# MCU.net
KiCad netlist of a schematic drawn in Altium Designer
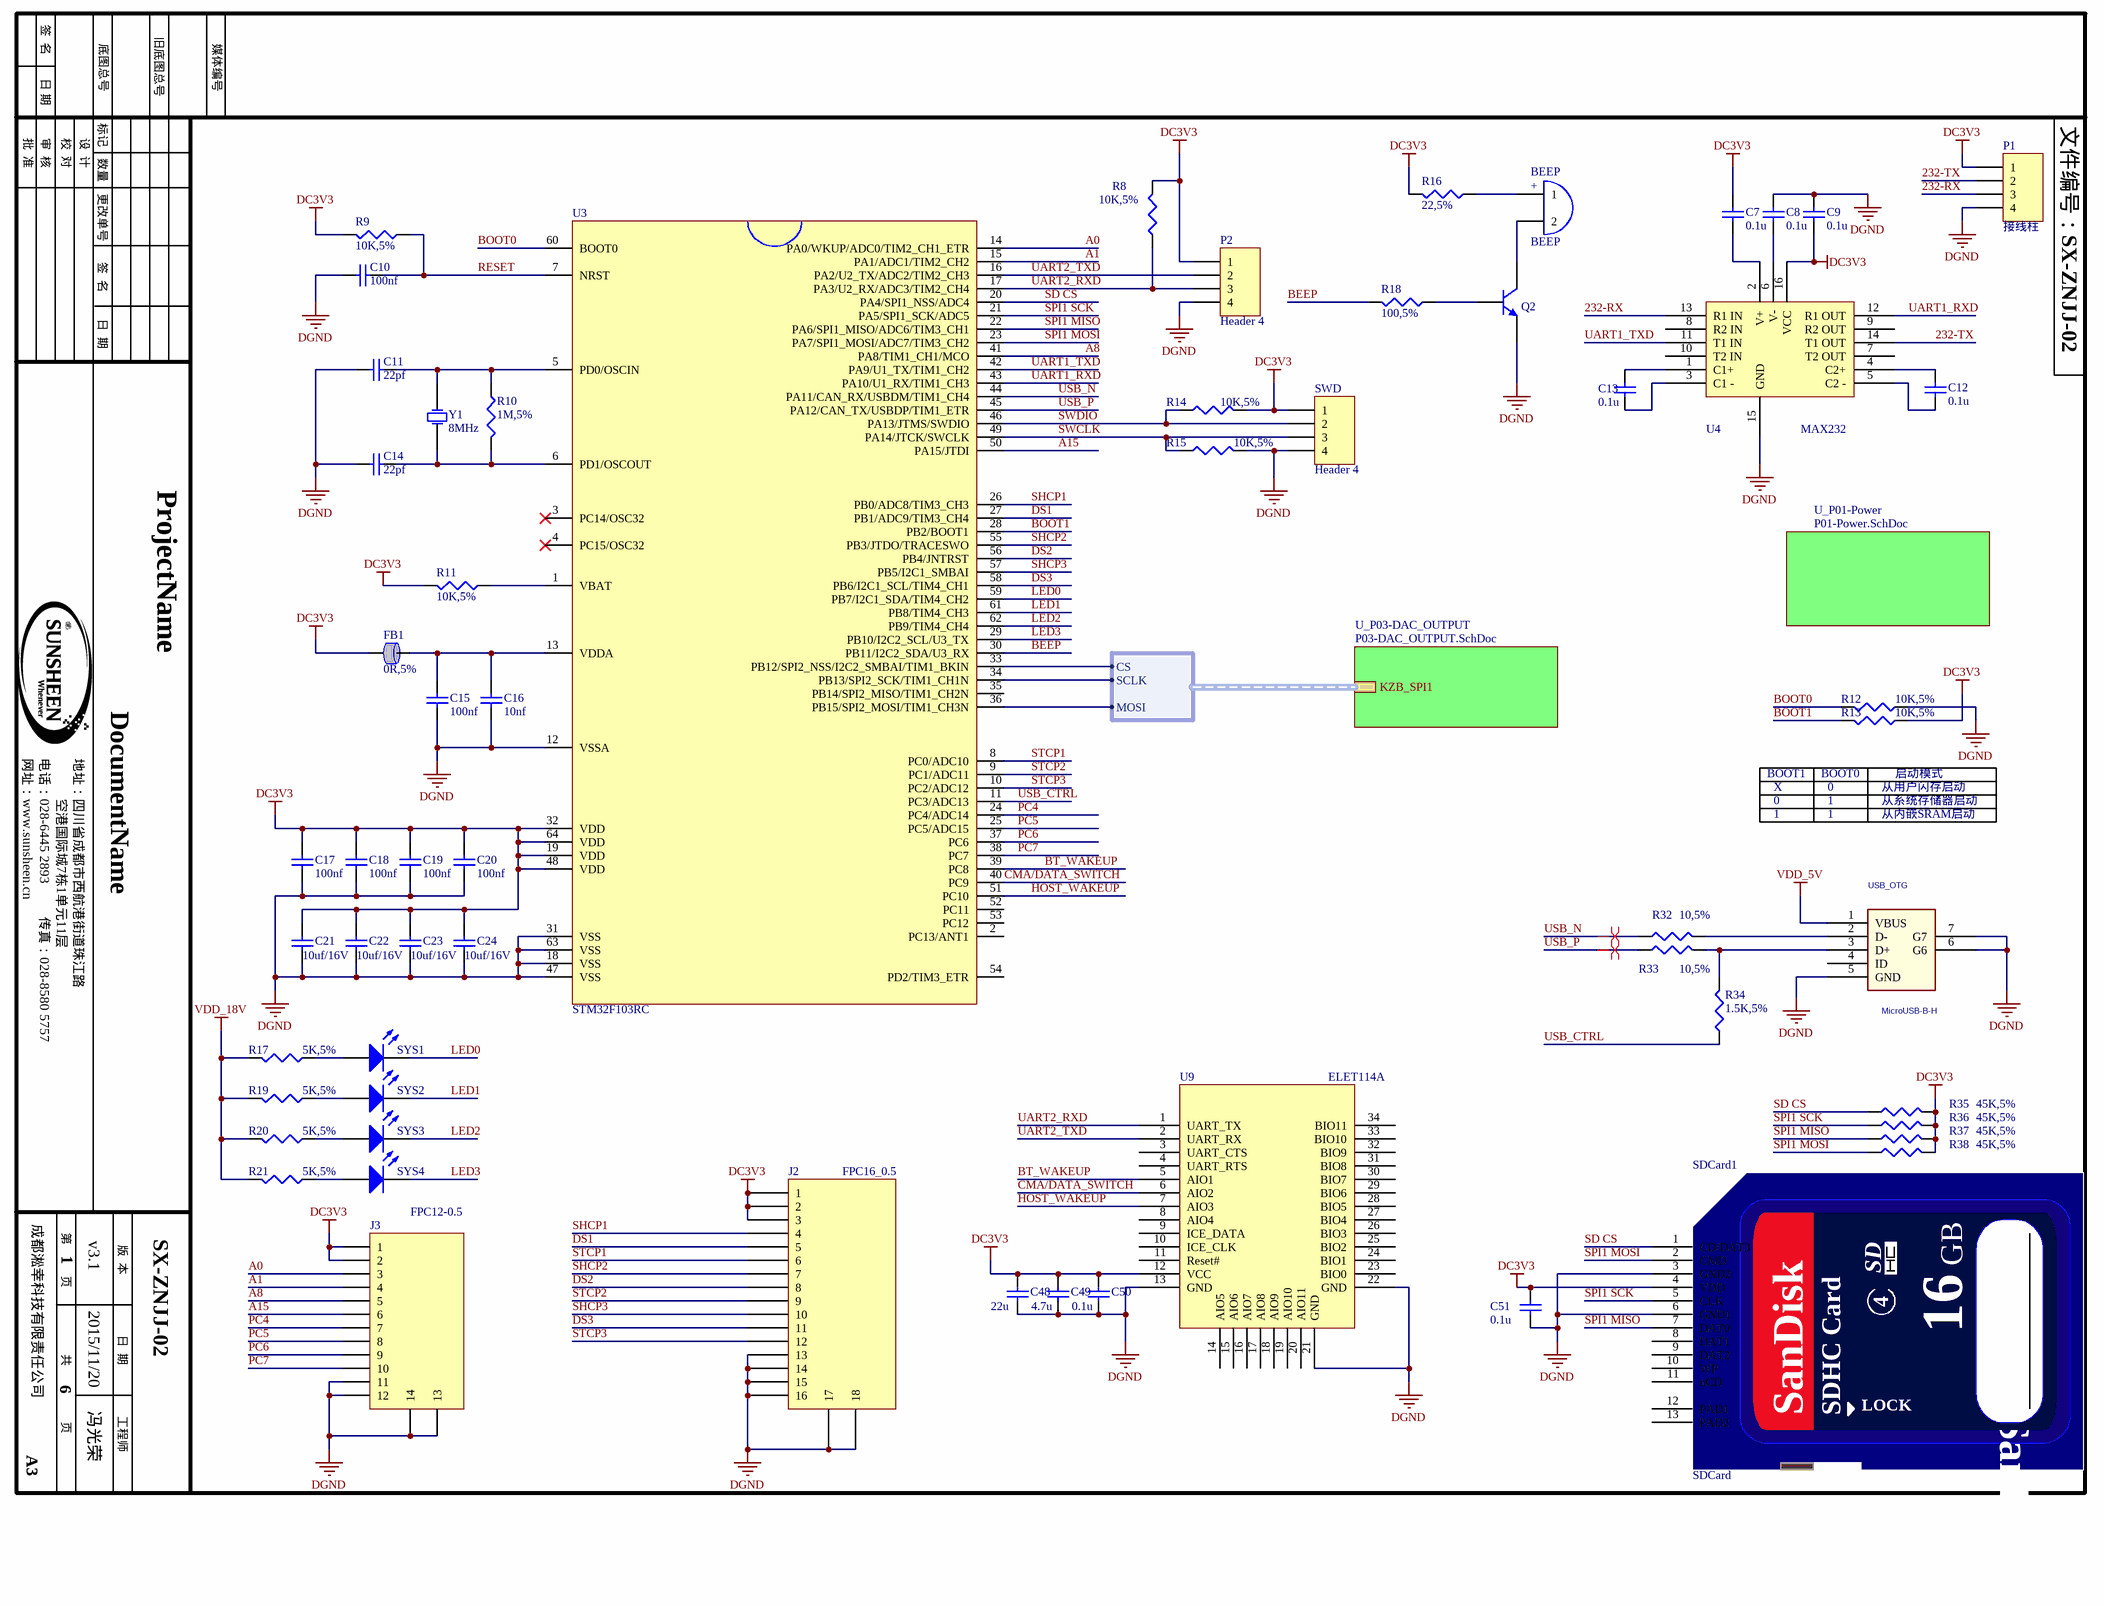
[diagram p0: MCU.SchDoc]

(export (version "E")
  (design (tool "Eeschema 10.0.6"))
  (components
    (comp (ref "BEEP") (value "BEEP") (footprint "蜂鸣器") (libsource (lib "常用库") (part "BELL")))
    (comp (ref "C7")
      (value "0.1u")
      (footprint "Cap0603")
      (description "无极性电容（表贴）")
      (libsource (lib "MyAD_Library") (part "Cap Semi"))
    )
    (comp (ref "C8")
      (value "0.1u")
      (footprint "Cap0603")
      (description "无极性电容（表贴）")
      (libsource (lib "MyAD_Library") (part "Cap Semi"))
    )
    (comp (ref "C9")
      (value "0.1u")
      (footprint "Cap0603")
      (description "无极性电容（表贴）")
      (libsource (lib "MyAD_Library") (part "Cap Semi"))
    )
    (comp (ref "C10")
      (value "100nf")
      (footprint "MyAD_Library:Cap0603")
      (description "无极性电容（表贴）")
      (libsource (lib "MyAD_Library") (part "Cap Semi"))
    )
    (comp (ref "C11")
      (value "22pf")
      (footprint "Cap0603")
      (description "无极性电容（表贴）")
      (libsource (lib "MyAD_Library") (part "Cap Semi"))
    )
    (comp (ref "C12")
      (value "0.1u")
      (footprint "Cap0603")
      (description "无极性电容（表贴）")
      (libsource (lib "MyAD_Library") (part "Cap Semi"))
    )
    (comp (ref "C13")
      (value "0.1u")
      (footprint "Cap0603")
      (description "无极性电容（表贴）")
      (libsource (lib "MyAD_Library") (part "Cap Semi"))
    )
    (comp (ref "C14")
      (value "22pf")
      (footprint "Cap0603")
      (description "无极性电容（表贴）")
      (libsource (lib "MyAD_Library") (part "Cap Semi"))
    )
    (comp (ref "C15")
      (value "100nf")
      (footprint "MyAD_Library:Cap0603")
      (description "无极性电容（表贴）")
      (libsource (lib "MyAD_Library") (part "Cap Semi"))
    )
    (comp (ref "C16")
      (value "10nf")
      (footprint "MyAD_Library:Cap0603")
      (description "无极性电容（表贴）")
      (libsource (lib "MyAD_Library") (part "Cap Semi"))
    )
    (comp (ref "C17")
      (value "100nf")
      (footprint "MyAD_Library:Cap0603")
      (description "无极性电容（表贴）")
      (libsource (lib "MyAD_Library") (part "Cap Semi"))
    )
    (comp (ref "C18")
      (value "100nf")
      (footprint "MyAD_Library:Cap0603")
      (description "无极性电容（表贴）")
      (libsource (lib "MyAD_Library") (part "Cap Semi"))
    )
    (comp (ref "C19")
      (value "100nf")
      (footprint "MyAD_Library:Cap0603")
      (description "无极性电容（表贴）")
      (libsource (lib "MyAD_Library") (part "Cap Semi"))
    )
    (comp (ref "C20")
      (value "100nf")
      (footprint "MyAD_Library:Cap0603")
      (description "无极性电容（表贴）")
      (libsource (lib "MyAD_Library") (part "Cap Semi"))
    )
    (comp (ref "C21")
      (value "10uf/16V")
      (footprint "Cap0603")
      (description "无极性电容（表贴）")
      (libsource (lib "MyAD_Library") (part "Cap Semi"))
    )
    (comp (ref "C22")
      (value "10uf/16V")
      (footprint "Cap0603")
      (description "无极性电容（表贴）")
      (libsource (lib "MyAD_Library") (part "Cap Semi"))
    )
    (comp (ref "C23")
      (value "10uf/16V")
      (footprint "Cap0603")
      (description "无极性电容（表贴）")
      (libsource (lib "MyAD_Library") (part "Cap Semi"))
    )
    (comp (ref "C24")
      (value "10uf/16V")
      (footprint "Cap0603")
      (description "无极性电容（表贴）")
      (libsource (lib "MyAD_Library") (part "Cap Semi"))
    )
    (comp (ref "C48")
      (value "22u")
      (footprint "Cap0603")
      (description "无极性电容（表贴）")
      (libsource (lib "MyAD_Library") (part "Cap Semi"))
    )
    (comp (ref "C49")
      (value "4.7u")
      (footprint "Cap0603")
      (description "无极性电容（表贴）")
      (libsource (lib "MyAD_Library") (part "Cap Semi"))
    )
    (comp (ref "C50")
      (value "0.1u")
      (footprint "Cap0603")
      (description "无极性电容（表贴）")
      (libsource (lib "MyAD_Library") (part "Cap Semi"))
    )
    (comp (ref "C51")
      (value "0.1u")
      (footprint "Cap0603")
      (description "无极性电容（表贴）")
      (libsource (lib "MyAD_Library") (part "Cap Semi"))
    )
    (comp (ref "FB1")
      (value "0R,5%")
      (footprint "FB0603")
      (description "磁珠")
      (libsource (lib "MyAD_Library") (part "FerriteBead"))
    )
    (comp (ref "J2")
      (value "FPC16_0.5")
      (footprint "FPC0.5-16P")
      (libsource (lib "MyAD_Schlib") (part "FPC16_0.5"))
    )
    (comp (ref "J3")
      (value "FPC12-0.5")
      (footprint "FPC0.5-12P")
      (libsource (lib "MyAD_Library") (part "FPC12-0.5"))
    )
    (comp (ref "P1")
      (value "接线柱")
      (footprint "4P接线柱5.08mm")
      (description "Header, 4-Pin")
      (libsource (lib "MyAD_Library") (part "Header 4"))
    )
    (comp (ref "P2")
      (value "Header 4")
      (footprint "HDR1X4")
      (description "Header, 4-Pin")
      (libsource (lib "MyAD_Library") (part "Header 4"))
    )
    (comp (ref "Q2")
      (value "S8050")
      (footprint "SOT-23B")
      (description "NPN")
      (libsource (lib "MyAD_Library") (part "S8050"))
    )
    (comp (ref "R8")
      (value "10K,5%")
      (footprint "Res0603")
      (description "电阻")
      (libsource (lib "MyAD_Library") (part "Res"))
    )
    (comp (ref "R9")
      (value "10K,5%")
      (footprint "Res0603")
      (description "电阻")
      (libsource (lib "MyAD_Library") (part "Res"))
    )
    (comp (ref "R10")
      (value "1M,5%")
      (footprint "Res0603")
      (description "电阻")
      (libsource (lib "MyAD_Library") (part "Res"))
    )
    (comp (ref "R11")
      (value "10K,5%")
      (footprint "Res0603")
      (description "电阻")
      (libsource (lib "MyAD_Library") (part "Res"))
    )
    (comp (ref "R12")
      (value "10K,5%")
      (footprint "Res0603")
      (description "电阻")
      (libsource (lib "MyAD_Library") (part "Res"))
    )
    (comp (ref "R13")
      (value "10K,5%")
      (footprint "Res0603")
      (description "电阻")
      (libsource (lib "MyAD_Library") (part "Res"))
    )
    (comp (ref "R14")
      (value "10K,5%")
      (footprint "Res0603")
      (description "电阻")
      (libsource (lib "MyAD_Library") (part "Res"))
    )
    (comp (ref "R15")
      (value "10K,5%")
      (footprint "Res0603")
      (description "电阻")
      (libsource (lib "MyAD_Library") (part "Res"))
    )
    (comp (ref "R16")
      (value "22,5%")
      (footprint "Res0603")
      (description "电阻")
      (libsource (lib "MyAD_Library") (part "Res"))
    )
    (comp (ref "R17")
      (value "5K,5%")
      (footprint "Res0603")
      (description "电阻")
      (libsource (lib "MyAD_Library") (part "Res"))
    )
    (comp (ref "R18")
      (value "100,5%")
      (footprint "Res0603")
      (description "电阻")
      (libsource (lib "MyAD_Library") (part "Res"))
    )
    (comp (ref "R19")
      (value "5K,5%")
      (footprint "Res0603")
      (description "电阻")
      (libsource (lib "MyAD_Library") (part "Res"))
    )
    (comp (ref "R20")
      (value "5K,5%")
      (footprint "Res0603")
      (description "电阻")
      (libsource (lib "MyAD_Library") (part "Res"))
    )
    (comp (ref "R21")
      (value "5K,5%")
      (footprint "Res0603")
      (description "电阻")
      (libsource (lib "MyAD_Library") (part "Res"))
    )
    (comp (ref "R32")
      (value "10,5%")
      (footprint "Res0603")
      (description "电阻")
      (libsource (lib "MyAD_Library") (part "Res"))
    )
    (comp (ref "R33")
      (value "10,5%")
      (footprint "Res0603")
      (description "电阻")
      (libsource (lib "MyAD_Library") (part "Res"))
    )
    (comp (ref "R34")
      (value "1.5K,5%")
      (footprint "Res0603")
      (description "电阻")
      (libsource (lib "MyAD_Library") (part "Res"))
    )
    (comp (ref "R35")
      (value "45K,5%")
      (footprint "Res0603")
      (description "电阻")
      (libsource (lib "MyAD_Library") (part "Res"))
    )
    (comp (ref "R36")
      (value "45K,5%")
      (footprint "Res0603")
      (description "电阻")
      (libsource (lib "MyAD_Library") (part "Res"))
    )
    (comp (ref "R37")
      (value "45K,5%")
      (footprint "Res0603")
      (description "电阻")
      (libsource (lib "MyAD_Library") (part "Res"))
    )
    (comp (ref "R38")
      (value "45K,5%")
      (footprint "Res0603")
      (description "电阻")
      (libsource (lib "MyAD_Library") (part "Res"))
    )
    (comp (ref "SDCard1")
      (value "SDCard")
      (footprint "SDCard")
      (description "SDCard插座")
      (libsource (lib "MyAD_Library") (part "SDCard"))
    )
    (comp (ref "SWD")
      (value "Header 4")
      (footprint "HDR1X4")
      (description "Header, 4-Pin")
      (fields (field (name "PUBLISHER") "Altium Limited"))
      (libsource (lib "Miscellaneous Connectors") (part "Header 4"))
    )
    (comp (ref "SYS1")
      (value "RED")
      (footprint "坐式LED")
      (description "Typical RED, GREEN, YELLOW, AMBER GaAs LED")
      (libsource (lib "MyAD_Library") (part "LED"))
    )
    (comp (ref "SYS2")
      (value "RED")
      (footprint "坐式LED")
      (description "Typical RED, GREEN, YELLOW, AMBER GaAs LED")
      (libsource (lib "MyAD_Library") (part "LED"))
    )
    (comp (ref "SYS3")
      (value "RED")
      (footprint "坐式LED")
      (description "Typical RED, GREEN, YELLOW, AMBER GaAs LED")
      (libsource (lib "MyAD_Library") (part "LED"))
    )
    (comp (ref "SYS4")
      (value "RED")
      (footprint "坐式LED")
      (description "Typical RED, GREEN, YELLOW, AMBER GaAs LED")
      (libsource (lib "MyAD_Library") (part "LED"))
    )
    (comp (ref "U3")
      (value "STM32F103RC")
      (footprint "QFP50P1200X1200X160-64N")
      (libsource (lib "MyAD_Library") (part "STM32F103RC"))
    )
    (comp (ref "U4")
      (value "MAX232")
      (footprint "SO-16")
      (description "+-15KV ESD-PROTECTED, +5V RS-232 TRANSCEIVERS")
      (libsource (lib "MISCESCH") (part "MAX232AEWE(16)"))
    )
    (comp (ref "U9") (value "ELET114A") (footprint "ELET114A") (libsource (lib "ELET114A") (part "ELET114A")))
    (comp (ref "USB_OTG")
      (value "MicroUSB-B-H")
      (footprint "PcbLib1:MICROUSB-B-H")
      (description "手机接口型USB")
      (libsource (lib "Schlib1") (part "MicroUSB-B-H"))
    )
    (comp (ref "Y1")
      (value "8MHz")
      (footprint "XTAL_49SMD")
      (description "晶体振荡器")
      (libsource (lib "MyAD_Library") (part "XTAL"))
    )
  )
  (nets
    (net (code "2") (name "/232-RX") (class "Default")
      (node (ref "P1") (pin "3") (pinfunction "3_3") (pintype "passive"))
      (node (ref "U4") (pin "13") (pinfunction "R1_IN_13") (pintype "passive"))
    )
    (net (code "3") (name "/232-TX") (class "Default")
      (node (ref "P1") (pin "2") (pinfunction "2_2") (pintype "passive"))
      (node (ref "U4") (pin "14") (pinfunction "T1_OUT_14") (pintype "passive"))
    )
    (net (code "4") (name "/A0") (class "Default")
      (node (ref "J3") (pin "3") (pinfunction "3_3") (pintype "passive"))
      (node (ref "U3") (pin "14") (pinfunction "PA0/WKUP/ADC0/TIM2_CH1_ETR_14") (pintype "passive"))
    )
    (net (code "5") (name "/A1") (class "Default")
      (node (ref "J3") (pin "4") (pinfunction "4_4") (pintype "passive"))
      (node (ref "U3") (pin "15") (pinfunction "PA1/ADC1/TIM2_CH2_15") (pintype "passive"))
    )
    (net (code "6") (name "/A8") (class "Default")
      (node (ref "J3") (pin "5") (pinfunction "5_5") (pintype "passive"))
      (node (ref "U3") (pin "41") (pinfunction "PA8/TIM1_CH1/MCO_41") (pintype "passive"))
    )
    (net (code "7") (name "/A15") (class "Default")
      (node (ref "J3") (pin "6") (pinfunction "6_6") (pintype "passive"))
      (node (ref "U3") (pin "50") (pinfunction "PA15/JTDI_50") (pintype "passive"))
    )
    (net (code "8") (name "/BEEP") (class "Default")
      (node (ref "R18") (pin "2") (pinfunction "2_2") (pintype "passive"))
      (node (ref "U3") (pin "30") (pinfunction "PB11/I2C2_SDA/U3_RX_30") (pintype "passive"))
    )
    (net (code "9") (name "/BOOT0") (class "Default")
      (node (ref "R12") (pin "2") (pinfunction "2_2") (pintype "passive"))
      (node (ref "U3") (pin "60") (pinfunction "BOOT0_60") (pintype "passive"))
    )
    (net (code "10") (name "/BOOT1") (class "Default")
      (node (ref "R13") (pin "2") (pinfunction "2_2") (pintype "passive"))
      (node (ref "U3") (pin "28") (pinfunction "PB2/BOOT1_28") (pintype "passive"))
    )
    (net (code "11") (name "/BT_WAKEUP") (class "Default")
      (node (ref "U3") (pin "39") (pinfunction "PC8_39") (pintype "passive"))
      (node (ref "U9") (pin "5") (pinfunction "AIO1_5") (pintype "passive"))
    )
    (net (code "12") (name "/CMA{slash}DATA_SWITCH") (class "Default")
      (node (ref "U3") (pin "40") (pinfunction "PC9_40") (pintype "passive"))
      (node (ref "U9") (pin "6") (pinfunction "AIO2_6") (pintype "passive"))
    )
    (net (code "13") (name "/CS") (class "Default")
      (node (ref "U3") (pin "33") (pinfunction "PB12/SPI2_NSS/I2C2_SMBAI/TIM1_BKIN_33") (pintype "passive"))
    )
    (net (code "14") (name "/DS1") (class "Default")
      (node (ref "J2") (pin "5") (pinfunction "5_5") (pintype "passive"))
      (node (ref "U3") (pin "27") (pinfunction "PB1/ADC9/TIM3_CH4_27") (pintype "passive"))
    )
    (net (code "15") (name "/DS2") (class "Default")
      (node (ref "J2") (pin "8") (pinfunction "8_8") (pintype "passive"))
      (node (ref "U3") (pin "56") (pinfunction "PB4/JNTRST_56") (pintype "passive"))
    )
    (net (code "16") (name "/DS3") (class "Default")
      (node (ref "J2") (pin "11") (pinfunction "11_11") (pintype "passive"))
      (node (ref "U3") (pin "58") (pinfunction "PB6/I2C1_SCL/TIM4_CH1_58") (pintype "passive"))
    )
    (net (code "17") (name "/HOST_WAKEUP") (class "Default")
      (node (ref "U3") (pin "51") (pinfunction "PC10_51") (pintype "passive"))
      (node (ref "U9") (pin "7") (pinfunction "AIO3_7") (pintype "passive"))
    )
    (net (code "18") (name "/LED0") (class "Default")
      (node (ref "SYS1") (pin "K") (pinfunction "K_K") (pintype "passive"))
      (node (ref "U3") (pin "59") (pinfunction "PB7/I2C1_SDA/TIM4_CH2_59") (pintype "passive"))
    )
    (net (code "19") (name "/LED1") (class "Default")
      (node (ref "SYS2") (pin "K") (pinfunction "K_K") (pintype "passive"))
      (node (ref "U3") (pin "61") (pinfunction "PB8/TIM4_CH3_61") (pintype "passive"))
    )
    (net (code "20") (name "/LED2") (class "Default")
      (node (ref "SYS3") (pin "K") (pinfunction "K_K") (pintype "passive"))
      (node (ref "U3") (pin "62") (pinfunction "PB9/TIM4_CH4_62") (pintype "passive"))
    )
    (net (code "21") (name "/LED3") (class "Default")
      (node (ref "SYS4") (pin "K") (pinfunction "K_K") (pintype "passive"))
      (node (ref "U3") (pin "29") (pinfunction "PB10/I2C2_SCL/U3_TX_29") (pintype "passive"))
    )
    (net (code "22") (name "/MOSI") (class "Default")
      (node (ref "U3") (pin "36") (pinfunction "PB15/SPI2_MOSI/TIM1_CH3N_36") (pintype "passive"))
    )
    (net (code "23") (name "/PC4") (class "Default")
      (node (ref "J3") (pin "7") (pinfunction "7_7") (pintype "passive"))
      (node (ref "U3") (pin "24") (pinfunction "PC4/ADC14_24") (pintype "passive"))
    )
    (net (code "24") (name "/PC5") (class "Default")
      (node (ref "J3") (pin "8") (pinfunction "8_8") (pintype "passive"))
      (node (ref "U3") (pin "25") (pinfunction "PC5/ADC15_25") (pintype "passive"))
    )
    (net (code "25") (name "/PC6") (class "Default")
      (node (ref "J3") (pin "9") (pinfunction "9_9") (pintype "passive"))
      (node (ref "U3") (pin "37") (pinfunction "PC6_37") (pintype "passive"))
    )
    (net (code "26") (name "/PC7") (class "Default")
      (node (ref "J3") (pin "10") (pinfunction "10_10") (pintype "passive"))
      (node (ref "U3") (pin "38") (pinfunction "PC7_38") (pintype "passive"))
    )
    (net (code "27") (name "/RESET") (class "Default")
      (node (ref "C10") (pin "2") (pinfunction "2_2") (pintype "passive"))
      (node (ref "R9") (pin "1") (pinfunction "1_1") (pintype "passive"))
      (node (ref "U3") (pin "7") (pinfunction "NRST_7") (pintype "passive"))
    )
    (net (code "28") (name "/SCLK") (class "Default")
      (node (ref "U3") (pin "34") (pinfunction "PB13/SPI2_SCK/TIM1_CH1N_34") (pintype "passive"))
    )
    (net (code "29") (name "/SD CS") (class "Default")
      (node (ref "R35") (pin "1") (pinfunction "1_1") (pintype "passive"))
      (node (ref "SDCard1") (pin "1") (pinfunction "CD/DAT3_1") (pintype "power_in"))
      (node (ref "U3") (pin "20") (pinfunction "PA4/SPI1_NSS/ADC4_20") (pintype "passive"))
    )
    (net (code "30") (name "/SHCP1") (class "Default")
      (node (ref "J2") (pin "4") (pinfunction "4_4") (pintype "passive"))
      (node (ref "U3") (pin "26") (pinfunction "PB0/ADC8/TIM3_CH3_26") (pintype "passive"))
    )
    (net (code "31") (name "/SHCP2") (class "Default")
      (node (ref "J2") (pin "7") (pinfunction "7_7") (pintype "passive"))
      (node (ref "U3") (pin "55") (pinfunction "PB3/JTDO/TRACESWO_55") (pintype "passive"))
    )
    (net (code "32") (name "/SHCP3") (class "Default")
      (node (ref "J2") (pin "10") (pinfunction "10_10") (pintype "passive"))
      (node (ref "U3") (pin "57") (pinfunction "PB5/I2C1_SMBAI_57") (pintype "passive"))
    )
    (net (code "33") (name "/SPI1 MISO") (class "Default")
      (node (ref "R37") (pin "1") (pinfunction "1_1") (pintype "passive"))
      (node (ref "SDCard1") (pin "7") (pinfunction "DAT0_7") (pintype "power_in"))
      (node (ref "U3") (pin "22") (pinfunction "PA6/SPI1_MISO/ADC6/TIM3_CH1_22") (pintype "passive"))
    )
    (net (code "34") (name "/SPI1 MOSI") (class "Default")
      (node (ref "R38") (pin "1") (pinfunction "1_1") (pintype "passive"))
      (node (ref "SDCard1") (pin "2") (pinfunction "CMD_2") (pintype "power_in"))
      (node (ref "U3") (pin "23") (pinfunction "PA7/SPI1_MOSI/ADC7/TIM3_CH2_23") (pintype "passive"))
    )
    (net (code "35") (name "/SPI1 SCK") (class "Default")
      (node (ref "R36") (pin "1") (pinfunction "1_1") (pintype "passive"))
      (node (ref "SDCard1") (pin "5") (pinfunction "CLK_5") (pintype "power_in"))
      (node (ref "U3") (pin "21") (pinfunction "PA5/SPI1_SCK/ADC5_21") (pintype "passive"))
    )
    (net (code "36") (name "/STCP1") (class "Default")
      (node (ref "J2") (pin "6") (pinfunction "6_6") (pintype "passive"))
      (node (ref "U3") (pin "8") (pinfunction "PC0/ADC10_8") (pintype "passive"))
    )
    (net (code "37") (name "/STCP2") (class "Default")
      (node (ref "J2") (pin "9") (pinfunction "9_9") (pintype "passive"))
      (node (ref "U3") (pin "9") (pinfunction "PC1/ADC11_9") (pintype "passive"))
    )
    (net (code "38") (name "/STCP3") (class "Default")
      (node (ref "J2") (pin "12") (pinfunction "12_12") (pintype "passive"))
      (node (ref "U3") (pin "10") (pinfunction "PC2/ADC12_10") (pintype "passive"))
    )
    (net (code "39") (name "/SWCLK") (class "Default")
      (node (ref "R15") (pin "1") (pinfunction "1_1") (pintype "passive"))
      (node (ref "SWD") (pin "3") (pinfunction "3_3") (pintype "passive"))
      (node (ref "U3") (pin "49") (pinfunction "PA14/JTCK/SWCLK_49") (pintype "passive"))
    )
    (net (code "40") (name "/SWDIO") (class "Default")
      (node (ref "R14") (pin "1") (pinfunction "1_1") (pintype "passive"))
      (node (ref "SWD") (pin "2") (pinfunction "2_2") (pintype "passive"))
      (node (ref "U3") (pin "46") (pinfunction "PA13/JTMS/SWDIO_46") (pintype "passive"))
    )
    (net (code "41") (name "/UART1_RXD") (class "Default")
      (node (ref "U3") (pin "43") (pinfunction "PA10/U1_RX/TIM1_CH3_43") (pintype "passive"))
      (node (ref "U4") (pin "12") (pinfunction "R1_OUT_12") (pintype "passive"))
    )
    (net (code "42") (name "/UART1_TXD") (class "Default")
      (node (ref "U3") (pin "42") (pinfunction "PA9/U1_TX/TIM1_CH2_42") (pintype "passive"))
      (node (ref "U4") (pin "11") (pinfunction "T1_IN_11") (pintype "passive"))
    )
    (net (code "43") (name "/UART2_RXD") (class "Default")
      (node (ref "P2") (pin "3") (pinfunction "3_3") (pintype "passive"))
      (node (ref "R8") (pin "1") (pinfunction "1_1") (pintype "passive"))
      (node (ref "U3") (pin "17") (pinfunction "PA3/U2_RX/ADC3/TIM2_CH4_17") (pintype "passive"))
      (node (ref "U9") (pin "1") (pinfunction "UART_TX_1") (pintype "passive"))
    )
    (net (code "44") (name "/UART2_TXD") (class "Default")
      (node (ref "P2") (pin "2") (pinfunction "2_2") (pintype "passive"))
      (node (ref "U3") (pin "16") (pinfunction "PA2/U2_TX/ADC2/TIM2_CH3_16") (pintype "passive"))
      (node (ref "U9") (pin "2") (pinfunction "UART_RX_2") (pintype "passive"))
    )
    (net (code "45") (name "/USB_CTRL") (class "Default")
      (node (ref "R34") (pin "1") (pinfunction "1_1") (pintype "passive"))
      (node (ref "U3") (pin "11") (pinfunction "PC3/ADC13_11") (pintype "passive"))
    )
    (net (code "46") (name "/USB_N") (class "Default")
      (node (ref "R32") (pin "1") (pinfunction "1_1") (pintype "passive"))
      (node (ref "U3") (pin "44") (pinfunction "PA11/CAN_RX/USBDM/TIM1_CH4_44") (pintype "passive"))
    )
    (net (code "47") (name "/USB_P") (class "Default")
      (node (ref "R33") (pin "1") (pinfunction "1_1") (pintype "passive"))
      (node (ref "U3") (pin "45") (pinfunction "PA12/CAN_TX/USBDP/TIM1_ETR_45") (pintype "passive"))
    )
    (net (code "49") (name "DC3V3") (class "Default")
      (node (ref "C17") (pin "2") (pinfunction "2_2") (pintype "passive"))
      (node (ref "C18") (pin "2") (pinfunction "2_2") (pintype "passive"))
      (node (ref "C19") (pin "2") (pinfunction "2_2") (pintype "passive"))
      (node (ref "C20") (pin "2") (pinfunction "2_2") (pintype "passive"))
      (node (ref "C21") (pin "2") (pinfunction "2_2") (pintype "passive"))
      (node (ref "C22") (pin "2") (pinfunction "2_2") (pintype "passive"))
      (node (ref "C23") (pin "2") (pinfunction "2_2") (pintype "passive"))
      (node (ref "C24") (pin "2") (pinfunction "2_2") (pintype "passive"))
      (node (ref "C48") (pin "2") (pinfunction "2_2") (pintype "passive"))
      (node (ref "C49") (pin "2") (pinfunction "2_2") (pintype "passive"))
      (node (ref "C50") (pin "2") (pinfunction "2_2") (pintype "passive"))
      (node (ref "C51") (pin "1") (pinfunction "1_1") (pintype "passive"))
      (node (ref "C7") (pin "2") (pinfunction "2_2") (pintype "passive"))
      (node (ref "C9") (pin "1") (pinfunction "1_1") (pintype "passive"))
      (node (ref "FB1") (pin "1") (pinfunction "1_1") (pintype "passive"))
      (node (ref "J2") (pin "1") (pinfunction "1_1") (pintype "passive"))
      (node (ref "J2") (pin "2") (pinfunction "2_2") (pintype "passive"))
      (node (ref "J2") (pin "3") (pinfunction "3_3") (pintype "passive"))
      (node (ref "J3") (pin "1") (pinfunction "1_1") (pintype "passive"))
      (node (ref "J3") (pin "2") (pinfunction "2_2") (pintype "passive"))
      (node (ref "P1") (pin "1") (pinfunction "1_1") (pintype "passive"))
      (node (ref "P2") (pin "1") (pinfunction "1_1") (pintype "passive"))
      (node (ref "R11") (pin "2") (pinfunction "2_2") (pintype "passive"))
      (node (ref "R13") (pin "1") (pinfunction "1_1") (pintype "passive"))
      (node (ref "R14") (pin "2") (pinfunction "2_2") (pintype "passive"))
      (node (ref "R16") (pin "2") (pinfunction "2_2") (pintype "passive"))
      (node (ref "R35") (pin "2") (pinfunction "2_2") (pintype "passive"))
      (node (ref "R36") (pin "2") (pinfunction "2_2") (pintype "passive"))
      (node (ref "R37") (pin "2") (pinfunction "2_2") (pintype "passive"))
      (node (ref "R38") (pin "2") (pinfunction "2_2") (pintype "passive"))
      (node (ref "R8") (pin "2") (pinfunction "2_2") (pintype "passive"))
      (node (ref "R9") (pin "2") (pinfunction "2_2") (pintype "passive"))
      (node (ref "SDCard1") (pin "4") (pinfunction "VDD_4") (pintype "power_in"))
      (node (ref "SWD") (pin "1") (pinfunction "1_1") (pintype "passive"))
      (node (ref "U3") (pin "19") (pinfunction "VDD_19") (pintype "passive"))
      (node (ref "U3") (pin "32") (pinfunction "VDD_32") (pintype "passive"))
      (node (ref "U3") (pin "48") (pinfunction "VDD_48") (pintype "passive"))
      (node (ref "U3") (pin "64") (pinfunction "VDD_64") (pintype "passive"))
      (node (ref "U4") (pin "16") (pinfunction "VCC_16") (pintype "passive"))
      (node (ref "U9") (pin "12") (pinfunction "VCC_12") (pintype "passive"))
    )
    (net (code "50") (name "DGND") (class "Default")
      (node (ref "C10") (pin "1") (pinfunction "1_1") (pintype "passive"))
      (node (ref "C11") (pin "1") (pinfunction "1_1") (pintype "passive"))
      (node (ref "C14") (pin "1") (pinfunction "1_1") (pintype "passive"))
      (node (ref "C15") (pin "1") (pinfunction "1_1") (pintype "passive"))
      (node (ref "C16") (pin "1") (pinfunction "1_1") (pintype "passive"))
      (node (ref "C17") (pin "1") (pinfunction "1_1") (pintype "passive"))
      (node (ref "C18") (pin "1") (pinfunction "1_1") (pintype "passive"))
      (node (ref "C19") (pin "1") (pinfunction "1_1") (pintype "passive"))
      (node (ref "C20") (pin "1") (pinfunction "1_1") (pintype "passive"))
      (node (ref "C21") (pin "1") (pinfunction "1_1") (pintype "passive"))
      (node (ref "C22") (pin "1") (pinfunction "1_1") (pintype "passive"))
      (node (ref "C23") (pin "1") (pinfunction "1_1") (pintype "passive"))
      (node (ref "C24") (pin "1") (pinfunction "1_1") (pintype "passive"))
      (node (ref "C48") (pin "1") (pinfunction "1_1") (pintype "passive"))
      (node (ref "C49") (pin "1") (pinfunction "1_1") (pintype "passive"))
      (node (ref "C50") (pin "1") (pinfunction "1_1") (pintype "passive"))
      (node (ref "C51") (pin "2") (pinfunction "2_2") (pintype "passive"))
      (node (ref "C8") (pin "2") (pinfunction "2_2") (pintype "passive"))
      (node (ref "C9") (pin "2") (pinfunction "2_2") (pintype "passive"))
      (node (ref "J2") (pin "13") (pinfunction "13_13") (pintype "passive"))
      (node (ref "J2") (pin "14") (pinfunction "14_14") (pintype "passive"))
      (node (ref "J2") (pin "15") (pinfunction "15_15") (pintype "passive"))
      (node (ref "J2") (pin "16") (pinfunction "16_16") (pintype "passive"))
      (node (ref "J2") (pin "17") (pinfunction "17_17") (pintype "passive"))
      (node (ref "J2") (pin "18") (pinfunction "18_18") (pintype "passive"))
      (node (ref "J3") (pin "11") (pinfunction "11_11") (pintype "passive"))
      (node (ref "J3") (pin "12") (pinfunction "12_12") (pintype "passive"))
      (node (ref "J3") (pin "13") (pinfunction "13_13") (pintype "passive"))
      (node (ref "J3") (pin "14") (pinfunction "14_14") (pintype "passive"))
      (node (ref "P1") (pin "4") (pinfunction "4_4") (pintype "passive"))
      (node (ref "P2") (pin "4") (pinfunction "4_4") (pintype "passive"))
      (node (ref "Q2") (pin "2") (pinfunction "E_2") (pintype "passive"))
      (node (ref "R12") (pin "1") (pinfunction "1_1") (pintype "passive"))
      (node (ref "R15") (pin "2") (pinfunction "2_2") (pintype "passive"))
      (node (ref "SDCard1") (pin "3") (pinfunction "GND2_3") (pintype "power_in"))
      (node (ref "SDCard1") (pin "6") (pinfunction "GND1_6") (pintype "power_in"))
      (node (ref "SWD") (pin "4") (pinfunction "4_4") (pintype "passive"))
      (node (ref "U3") (pin "12") (pinfunction "VSSA_12") (pintype "passive"))
      (node (ref "U3") (pin "18") (pinfunction "VSS_18") (pintype "passive"))
      (node (ref "U3") (pin "31") (pinfunction "VSS_31") (pintype "passive"))
      (node (ref "U3") (pin "47") (pinfunction "VSS_47") (pintype "passive"))
      (node (ref "U3") (pin "63") (pinfunction "VSS_63") (pintype "passive"))
      (node (ref "U4") (pin "15") (pinfunction "GND_15") (pintype "passive"))
      (node (ref "U9") (pin "13") (pinfunction "GND_13") (pintype "passive"))
      (node (ref "U9") (pin "21") (pinfunction "GND_21") (pintype "passive"))
      (node (ref "U9") (pin "22") (pinfunction "GND_22") (pintype "passive"))
      (node (ref "USB_OTG") (pin "5") (pinfunction "GND_5") (pintype "passive"))
      (node (ref "USB_OTG") (pin "6") (pinfunction "G6_6") (pintype "passive"))
      (node (ref "USB_OTG") (pin "7") (pinfunction "G7_7") (pintype "passive"))
    )
    (net (code "51") (name "Net-(BEEP-Pad1)") (class "Default")
      (node (ref "BEEP") (pin "1") (pinfunction "1_1") (pintype "passive"))
      (node (ref "R16") (pin "1") (pinfunction "1_1") (pintype "passive"))
    )
    (net (code "52") (name "Net-(Q2-B)") (class "Default")
      (node (ref "Q2") (pin "1") (pinfunction "B_1") (pintype "passive"))
      (node (ref "R18") (pin "1") (pinfunction "1_1") (pintype "passive"))
    )
    (net (code "53") (name "Net-(Q2-C)") (class "Default")
      (node (ref "BEEP") (pin "2") (pinfunction "2_2") (pintype "passive"))
      (node (ref "Q2") (pin "3") (pinfunction "C_3") (pintype "passive"))
    )
    (net (code "54") (name "Net-(R17-Pad2)") (class "Default")
      (node (ref "R17") (pin "2") (pinfunction "2_2") (pintype "passive"))
      (node (ref "SYS1") (pin "A") (pinfunction "A_A") (pintype "passive"))
    )
    (net (code "55") (name "Net-(R19-Pad2)") (class "Default")
      (node (ref "R19") (pin "2") (pinfunction "2_2") (pintype "passive"))
      (node (ref "SYS2") (pin "A") (pinfunction "A_A") (pintype "passive"))
    )
    (net (code "56") (name "Net-(R20-Pad2)") (class "Default")
      (node (ref "R20") (pin "2") (pinfunction "2_2") (pintype "passive"))
      (node (ref "SYS3") (pin "A") (pinfunction "A_A") (pintype "passive"))
    )
    (net (code "57") (name "Net-(R21-Pad2)") (class "Default")
      (node (ref "R21") (pin "2") (pinfunction "2_2") (pintype "passive"))
      (node (ref "SYS4") (pin "A") (pinfunction "A_A") (pintype "passive"))
    )
    (net (code "58") (name "Net-(U3-PD0{slash}OSCIN)") (class "Default")
      (node (ref "C11") (pin "2") (pinfunction "2_2") (pintype "passive"))
      (node (ref "R10") (pin "1") (pinfunction "1_1") (pintype "passive"))
      (node (ref "U3") (pin "5") (pinfunction "PD0/OSCIN_5") (pintype "passive"))
      (node (ref "Y1") (pin "1") (pinfunction "OSC1_1") (pintype "passive"))
    )
    (net (code "59") (name "Net-(U3-PD1{slash}OSCOUT)") (class "Default")
      (node (ref "C14") (pin "2") (pinfunction "2_2") (pintype "passive"))
      (node (ref "R10") (pin "2") (pinfunction "2_2") (pintype "passive"))
      (node (ref "U3") (pin "6") (pinfunction "PD1/OSCOUT_6") (pintype "passive"))
      (node (ref "Y1") (pin "2") (pinfunction "OSC2_2") (pintype "passive"))
    )
    (net (code "60") (name "Net-(U3-VBAT)") (class "Default")
      (node (ref "R11") (pin "1") (pinfunction "1_1") (pintype "passive"))
      (node (ref "U3") (pin "1") (pinfunction "VBAT_1") (pintype "passive"))
    )
    (net (code "61") (name "Net-(U3-VDDA)") (class "Default")
      (node (ref "C15") (pin "2") (pinfunction "2_2") (pintype "passive"))
      (node (ref "C16") (pin "2") (pinfunction "2_2") (pintype "passive"))
      (node (ref "FB1") (pin "2") (pinfunction "2_2") (pintype "passive"))
      (node (ref "U3") (pin "13") (pinfunction "VDDA_13") (pintype "passive"))
    )
    (net (code "62") (name "Net-(U4-C1+)") (class "Default")
      (node (ref "C13") (pin "2") (pinfunction "2_2") (pintype "passive"))
      (node (ref "U4") (pin "1") (pinfunction "C1+_1") (pintype "passive"))
    )
    (net (code "63") (name "Net-(U4-C1_-)") (class "Default")
      (node (ref "C13") (pin "1") (pinfunction "1_1") (pintype "passive"))
      (node (ref "U4") (pin "3") (pinfunction "C1_-_3") (pintype "passive"))
    )
    (net (code "64") (name "Net-(U4-C2+)") (class "Default")
      (node (ref "C12") (pin "2") (pinfunction "2_2") (pintype "passive"))
      (node (ref "U4") (pin "4") (pinfunction "C2+_4") (pintype "passive"))
    )
    (net (code "65") (name "Net-(U4-C2_-)") (class "Default")
      (node (ref "C12") (pin "1") (pinfunction "1_1") (pintype "passive"))
      (node (ref "U4") (pin "5") (pinfunction "C2_-_5") (pintype "passive"))
    )
    (net (code "66") (name "Net-(U4-V+)") (class "Default")
      (node (ref "C7") (pin "1") (pinfunction "1_1") (pintype "passive"))
      (node (ref "U4") (pin "2") (pinfunction "V+_2") (pintype "passive"))
    )
    (net (code "67") (name "Net-(U4-V-)") (class "Default")
      (node (ref "C8") (pin "1") (pinfunction "1_1") (pintype "passive"))
      (node (ref "U4") (pin "6") (pinfunction "V-_6") (pintype "passive"))
    )
    (net (code "68") (name "Net-(USB_OTG-D+)") (class "Default")
      (node (ref "R33") (pin "2") (pinfunction "2_2") (pintype "passive"))
      (node (ref "R34") (pin "2") (pinfunction "2_2") (pintype "passive"))
      (node (ref "USB_OTG") (pin "3") (pinfunction "D+_3") (pintype "passive"))
    )
    (net (code "69") (name "Net-(USB_OTG-D-)") (class "Default")
      (node (ref "R32") (pin "2") (pinfunction "2_2") (pintype "passive"))
      (node (ref "USB_OTG") (pin "2") (pinfunction "D-_2") (pintype "passive"))
    )
    (net (code "70") (name "VDD_5V") (class "Default")
      (node (ref "USB_OTG") (pin "1") (pinfunction "VBUS_1") (pintype "passive"))
    )
    (net (code "71") (name "VDD_18V") (class "Default")
      (node (ref "R17") (pin "1") (pinfunction "1_1") (pintype "passive"))
      (node (ref "R19") (pin "1") (pinfunction "1_1") (pintype "passive"))
      (node (ref "R20") (pin "1") (pinfunction "1_1") (pintype "passive"))
      (node (ref "R21") (pin "1") (pinfunction "1_1") (pintype "passive"))
    )
    (net (code "72") (name "unconnected-(SDCard1-DAT1-Pad8)") (class "Default")
      (node (ref "SDCard1") (pin "8") (pinfunction "DAT1_8") (pintype "power_in"))
    )
    (net (code "73") (name "unconnected-(SDCard1-DAT2-Pad9)") (class "Default")
      (node (ref "SDCard1") (pin "9") (pinfunction "DAT2_9") (pintype "power_in"))
    )
    (net (code "74") (name "unconnected-(SDCard1-PAD1-Pad12)") (class "Default")
      (node (ref "SDCard1") (pin "12") (pinfunction "PAD1_12") (pintype "power_in"))
    )
    (net (code "75") (name "unconnected-(SDCard1-PAD2-Pad13)") (class "Default")
      (node (ref "SDCard1") (pin "13") (pinfunction "PAD2_13") (pintype "power_in"))
    )
    (net (code "76") (name "unconnected-(SDCard1-WP-Pad10)") (class "Default")
      (node (ref "SDCard1") (pin "10") (pinfunction "WP_10") (pintype "power_in"))
    )
    (net (code "77") (name "unconnected-(SDCard1-nCD-Pad11)") (class "Default")
      (node (ref "SDCard1") (pin "11") (pinfunction "nCD_11") (pintype "power_in"))
    )
    (net (code "78") (name "unconnected-(U3-PB14{slash}SPI2_MISO{slash}TIM1_CH2N-Pad35)") (class "Default")
      (node (ref "U3") (pin "35") (pinfunction "PB14/SPI2_MISO/TIM1_CH2N_35") (pintype "passive"))
    )
    (net (code "79") (name "unconnected-(U3-PC11-Pad52)") (class "Default")
      (node (ref "U3") (pin "52") (pinfunction "PC11_52") (pintype "passive"))
    )
    (net (code "80") (name "unconnected-(U3-PC12-Pad53)") (class "Default")
      (node (ref "U3") (pin "53") (pinfunction "PC12_53") (pintype "passive"))
    )
    (net (code "81") (name "unconnected-(U3-PC13{slash}ANT1-Pad2)") (class "Default")
      (node (ref "U3") (pin "2") (pinfunction "PC13/ANT1_2") (pintype "passive"))
    )
    (net (code "82") (name "unconnected-(U3-PC14{slash}OSC32-Pad3)") (class "Default")
      (node (ref "U3") (pin "3") (pinfunction "PC14/OSC32_3") (pintype "passive+no_connect"))
    )
    (net (code "83") (name "unconnected-(U3-PC15{slash}OSC32-Pad4)") (class "Default")
      (node (ref "U3") (pin "4") (pinfunction "PC15/OSC32_4") (pintype "passive+no_connect"))
    )
    (net (code "84") (name "unconnected-(U3-PD2{slash}TIM3_ETR-Pad54)") (class "Default")
      (node (ref "U3") (pin "54") (pinfunction "PD2/TIM3_ETR_54") (pintype "passive"))
    )
    (net (code "85") (name "unconnected-(U4-R2_IN-Pad8)") (class "Default")
      (node (ref "U4") (pin "8") (pinfunction "R2_IN_8") (pintype "passive"))
    )
    (net (code "86") (name "unconnected-(U4-R2_OUT-Pad9)") (class "Default")
      (node (ref "U4") (pin "9") (pinfunction "R2_OUT_9") (pintype "passive"))
    )
    (net (code "87") (name "unconnected-(U4-T2_IN-Pad10)") (class "Default")
      (node (ref "U4") (pin "10") (pinfunction "T2_IN_10") (pintype "passive"))
    )
    (net (code "88") (name "unconnected-(U4-T2_OUT-Pad7)") (class "Default")
      (node (ref "U4") (pin "7") (pinfunction "T2_OUT_7") (pintype "passive"))
    )
    (net (code "89") (name "unconnected-(U9-AIO4-Pad8)") (class "Default")
      (node (ref "U9") (pin "8") (pinfunction "AIO4_8") (pintype "passive"))
    )
    (net (code "90") (name "unconnected-(U9-AIO5-Pad14)") (class "Default")
      (node (ref "U9") (pin "14") (pinfunction "AIO5_14") (pintype "passive"))
    )
    (net (code "91") (name "unconnected-(U9-AIO6-Pad15)") (class "Default")
      (node (ref "U9") (pin "15") (pinfunction "AIO6_15") (pintype "passive"))
    )
    (net (code "92") (name "unconnected-(U9-AIO7-Pad16)") (class "Default")
      (node (ref "U9") (pin "16") (pinfunction "AIO7_16") (pintype "passive"))
    )
    (net (code "93") (name "unconnected-(U9-AIO8-Pad17)") (class "Default")
      (node (ref "U9") (pin "17") (pinfunction "AIO8_17") (pintype "passive"))
    )
    (net (code "94") (name "unconnected-(U9-AIO9-Pad18)") (class "Default")
      (node (ref "U9") (pin "18") (pinfunction "AIO9_18") (pintype "passive"))
    )
    (net (code "95") (name "unconnected-(U9-AIO10-Pad19)") (class "Default")
      (node (ref "U9") (pin "19") (pinfunction "AIO10_19") (pintype "passive"))
    )
    (net (code "96") (name "unconnected-(U9-AIO11-Pad20)") (class "Default")
      (node (ref "U9") (pin "20") (pinfunction "AIO11_20") (pintype "passive"))
    )
    (net (code "97") (name "unconnected-(U9-BIO0-Pad23)") (class "Default")
      (node (ref "U9") (pin "23") (pinfunction "BIO0_23") (pintype "passive"))
    )
    (net (code "98") (name "unconnected-(U9-BIO1-Pad24)") (class "Default")
      (node (ref "U9") (pin "24") (pinfunction "BIO1_24") (pintype "passive"))
    )
    (net (code "99") (name "unconnected-(U9-BIO2-Pad25)") (class "Default")
      (node (ref "U9") (pin "25") (pinfunction "BIO2_25") (pintype "passive"))
    )
    (net (code "100") (name "unconnected-(U9-BIO3-Pad26)") (class "Default")
      (node (ref "U9") (pin "26") (pinfunction "BIO3_26") (pintype "passive"))
    )
    (net (code "101") (name "unconnected-(U9-BIO4-Pad27)") (class "Default")
      (node (ref "U9") (pin "27") (pinfunction "BIO4_27") (pintype "passive"))
    )
    (net (code "102") (name "unconnected-(U9-BIO5-Pad28)") (class "Default")
      (node (ref "U9") (pin "28") (pinfunction "BIO5_28") (pintype "passive"))
    )
    (net (code "103") (name "unconnected-(U9-BIO6-Pad29)") (class "Default")
      (node (ref "U9") (pin "29") (pinfunction "BIO6_29") (pintype "passive"))
    )
    (net (code "104") (name "unconnected-(U9-BIO7-Pad30)") (class "Default")
      (node (ref "U9") (pin "30") (pinfunction "BIO7_30") (pintype "passive"))
    )
    (net (code "105") (name "unconnected-(U9-BIO8-Pad31)") (class "Default")
      (node (ref "U9") (pin "31") (pinfunction "BIO8_31") (pintype "passive"))
    )
    (net (code "106") (name "unconnected-(U9-BIO9-Pad32)") (class "Default")
      (node (ref "U9") (pin "32") (pinfunction "BIO9_32") (pintype "passive"))
    )
    (net (code "107") (name "unconnected-(U9-BIO10-Pad33)") (class "Default")
      (node (ref "U9") (pin "33") (pinfunction "BIO10_33") (pintype "passive"))
    )
    (net (code "108") (name "unconnected-(U9-BIO11-Pad34)") (class "Default")
      (node (ref "U9") (pin "34") (pinfunction "BIO11_34") (pintype "passive"))
    )
    (net (code "109") (name "unconnected-(U9-ICE_CLK-Pad10)") (class "Default")
      (node (ref "U9") (pin "10") (pinfunction "ICE_CLK_10") (pintype "passive"))
    )
    (net (code "110") (name "unconnected-(U9-ICE_DATA-Pad9)") (class "Default")
      (node (ref "U9") (pin "9") (pinfunction "ICE_DATA_9") (pintype "passive"))
    )
    (net (code "111") (name "unconnected-(U9-Reset#-Pad11)") (class "Default")
      (node (ref "U9") (pin "11") (pinfunction "Reset#_11") (pintype "passive"))
    )
    (net (code "112") (name "unconnected-(U9-UART_CTS-Pad3)") (class "Default")
      (node (ref "U9") (pin "3") (pinfunction "UART_CTS_3") (pintype "passive"))
    )
    (net (code "113") (name "unconnected-(U9-UART_RTS-Pad4)") (class "Default")
      (node (ref "U9") (pin "4") (pinfunction "UART_RTS_4") (pintype "passive"))
    )
    (net (code "114") (name "unconnected-(USB_OTG-ID-Pad4)") (class "Default")
      (node (ref "USB_OTG") (pin "4") (pinfunction "ID_4") (pintype "passive"))
    )
  )
)
